# Step_Down_Module.net
KiCad netlist of a schematic drawn in EAGLE
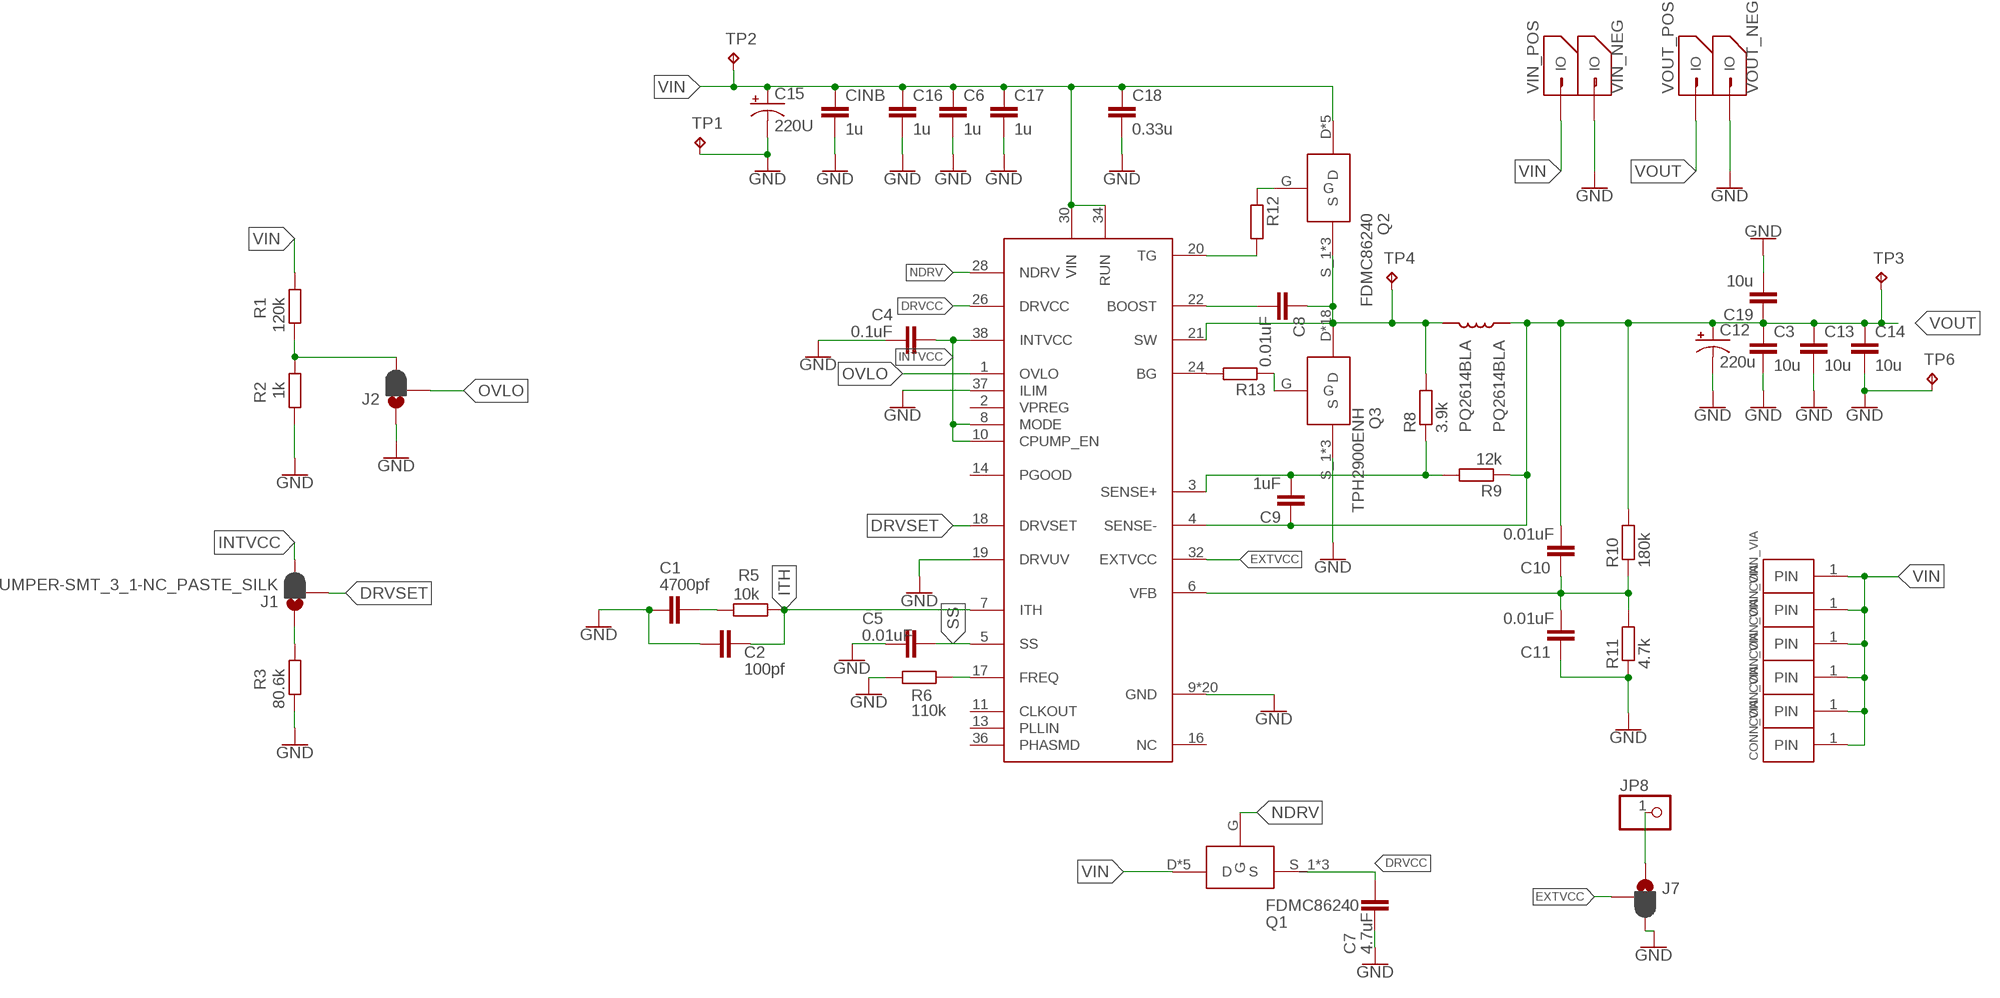
[diagram p0: schematic, sheet 1]

(export (version "E")
  (design (tool "Eeschema 10.0.6"))
  (components
    (comp (ref "C1")
      (value "4700pf")
      (footprint "eagle-import:C0805")
      (libsource (lib "eagle-import") (part "C-EUC0805"))
    )
    (comp (ref "C2")
      (value "100pf")
      (footprint "eagle-import:C0805")
      (libsource (lib "eagle-import") (part "C-EUC0805"))
    )
    (comp (ref "C3")
      (value "10u")
      (footprint "eagle-import:1210")
      (libsource (lib "eagle-import") (part "CAP_SMD_1210"))
    )
    (comp (ref "C4")
      (value "0.1uF")
      (footprint "eagle-import:C0805")
      (libsource (lib "eagle-import") (part "C-EUC0805"))
    )
    (comp (ref "C5")
      (value "0.01uF")
      (footprint "eagle-import:C0805")
      (libsource (lib "eagle-import") (part "C-EUC0805"))
    )
    (comp (ref "C6")
      (value "1u")
      (footprint "eagle-import:C2220K")
      (libsource (lib "eagle-import") (part "C-EUC2220K"))
    )
    (comp (ref "C7")
      (value "4.7uF")
      (footprint "eagle-import:C0805")
      (libsource (lib "eagle-import") (part "C-EUC0805"))
    )
    (comp (ref "C8")
      (value "0.01uF")
      (footprint "eagle-import:C0805")
      (libsource (lib "eagle-import") (part "C-EUC0805"))
    )
    (comp (ref "C9")
      (value "1uF")
      (footprint "eagle-import:C0805")
      (libsource (lib "eagle-import") (part "C-EUC0805"))
    )
    (comp (ref "C10")
      (value "0.01uF")
      (footprint "eagle-import:C0805")
      (libsource (lib "eagle-import") (part "C-EUC0805"))
    )
    (comp (ref "C11")
      (value "0.01uF")
      (footprint "eagle-import:C0805")
      (libsource (lib "eagle-import") (part "C-EUC0805"))
    )
    (comp (ref "C12")
      (value "220u")
      (footprint "eagle-import:CPOL-RADIAL-5MM-10MM")
      (libsource (lib "eagle-import") (part "1000UF-RADIAL-5MM-25V-20%"))
    )
    (comp (ref "C13")
      (value "10u")
      (footprint "eagle-import:1210")
      (libsource (lib "eagle-import") (part "CAP_SMD_1210"))
    )
    (comp (ref "C14")
      (value "10u")
      (footprint "eagle-import:1210")
      (libsource (lib "eagle-import") (part "CAP_SMD_1210"))
    )
    (comp (ref "C15")
      (value "220U")
      (footprint "eagle-import:CPOL-RADIAL-7.5MM-18MM")
      (libsource (lib "eagle-import") (part "220U"))
    )
    (comp (ref "C16")
      (value "1u")
      (footprint "eagle-import:C2220K")
      (libsource (lib "eagle-import") (part "C-EUC2220K"))
    )
    (comp (ref "C17")
      (value "1u")
      (footprint "eagle-import:C2220K")
      (libsource (lib "eagle-import") (part "C-EUC2220K"))
    )
    (comp (ref "C18")
      (value "0.33u")
      (footprint "eagle-import:C1812")
      (libsource (lib "eagle-import") (part "C-EUC1812"))
    )
    (comp (ref "C19")
      (value "10u")
      (footprint "eagle-import:1210")
      (libsource (lib "eagle-import") (part "CAP_SMD_1210"))
    )
    (comp (ref "CINB")
      (value "1u")
      (footprint "eagle-import:C2220K")
      (libsource (lib "eagle-import") (part "C-EUC2220K"))
    )
    (comp (ref "J1")
      (value "JUMPER-SMT_3_1-NC_PASTE_SILK")
      (footprint "eagle-import:SMT-JUMPER_3_1-NC_PASTE_SILK")
      (libsource (lib "eagle-import") (part "JUMPER-SMT_3_1-NC_PASTE_SILK"))
    )
    (comp (ref "J2")
      (value "JUMPER-SMT_3_1-NC_PASTE_SILK")
      (footprint "eagle-import:SMT-JUMPER_3_1-NC_PASTE_SILK")
      (libsource (lib "eagle-import") (part "JUMPER-SMT_3_1-NC_PASTE_SILK"))
    )
    (comp (ref "J7")
      (value "JUMPER-SMT_3_1-NC_PASTE_SILK")
      (footprint "eagle-import:SMT-JUMPER_3_1-NC_PASTE_SILK")
      (libsource (lib "eagle-import") (part "JUMPER-SMT_3_1-NC_PASTE_SILK"))
    )
    (comp (ref "JP8")
      (value "PINHD-1X1")
      (footprint "eagle-import:1X01")
      (libsource (lib "eagle-import") (part "PINHD-1X1"))
    )
    (comp (ref "L1")
      (value "PQ2614BLA")
      (footprint "eagle-import:PQ2614BLA")
      (libsource (lib "eagle-import") (part "PQ2614BLA"))
    )
    (comp (ref "Q1")
      (value "FDMC86240")
      (footprint "eagle-import:8-MLP_POWERWFDN")
      (libsource (lib "eagle-import") (part "FDMC86240"))
    )
    (comp (ref "Q2")
      (value "FDMC86240")
      (footprint "eagle-import:8-MLP_POWERWFDN")
      (libsource (lib "eagle-import") (part "FDMC86240"))
    )
    (comp (ref "Q3")
      (value "TPH2900ENH")
      (footprint "eagle-import:SOP_ADVANCE")
      (fields
        (field (name "MANUFACTURER_PART_NUMBER") "TPH8R80ANH")
        (field (name "MOUSER_PART_NUMBER") "1687790")
        (field (name "SPICEPREFIX") "Q")
      )
      (libsource (lib "eagle-import") (part "TPH2900ENH"))
    )
    (comp (ref "R1")
      (value "120k")
      (footprint "eagle-import:R0805")
      (libsource (lib "eagle-import") (part "R-EU_R0805"))
    )
    (comp (ref "R2")
      (value "1k")
      (footprint "eagle-import:R0805")
      (libsource (lib "eagle-import") (part "R-EU_R0805"))
    )
    (comp (ref "R3")
      (value "80.6k")
      (footprint "eagle-import:R0805")
      (libsource (lib "eagle-import") (part "R-EU_R0805"))
    )
    (comp (ref "R5")
      (value "10k")
      (footprint "eagle-import:R0805")
      (libsource (lib "eagle-import") (part "R-EU_R0805"))
    )
    (comp (ref "R6")
      (value "110k")
      (footprint "eagle-import:R0805")
      (libsource (lib "eagle-import") (part "R-EU_R0805"))
    )
    (comp (ref "R8")
      (value "3.9k")
      (footprint "eagle-import:0204_5")
      (libsource (lib "eagle-import") (part "resistor_348_R-EU_0204/5"))
    )
    (comp (ref "R9")
      (value "12k")
      (footprint "eagle-import:0204_5")
      (libsource (lib "eagle-import") (part "resistor_348_R-EU_0204/5"))
    )
    (comp (ref "R10")
      (value "180k")
      (footprint "eagle-import:R0805")
      (libsource (lib "eagle-import") (part "R-EU_R0805"))
    )
    (comp (ref "R11")
      (value "4.7k")
      (footprint "eagle-import:R0805")
      (libsource (lib "eagle-import") (part "R-EU_R0805"))
    )
    (comp (ref "R12")
      (value "R-EU_R0805")
      (footprint "eagle-import:R0805")
      (libsource (lib "eagle-import") (part "R-EU_R0805"))
    )
    (comp (ref "R13")
      (value "R-EU_R0805")
      (footprint "eagle-import:R0805")
      (libsource (lib "eagle-import") (part "R-EU_R0805"))
    )
    (comp (ref "TP1")
      (value "TPTP16R")
      (footprint "eagle-import:TP16R")
      (libsource (lib "eagle-import") (part "TPTP16R"))
    )
    (comp (ref "TP2")
      (value "TPTP16R")
      (footprint "eagle-import:TP16R")
      (libsource (lib "eagle-import") (part "TPTP16R"))
    )
    (comp (ref "TP3")
      (value "TPTP16R")
      (footprint "eagle-import:TP16R")
      (libsource (lib "eagle-import") (part "TPTP16R"))
    )
    (comp (ref "TP4")
      (value "TPTP16R")
      (footprint "eagle-import:TP16R")
      (libsource (lib "eagle-import") (part "TPTP16R"))
    )
    (comp (ref "TP6")
      (value "TPTP16R")
      (footprint "eagle-import:TP16R")
      (libsource (lib "eagle-import") (part "TPTP16R"))
    )
    (comp (ref "U$1")
      (value "CONN_VIA")
      (footprint "eagle-import:CONN_VIA")
      (libsource (lib "eagle-import") (part "CONN_VIA"))
    )
    (comp (ref "U$2")
      (value "CONN_VIA")
      (footprint "eagle-import:CONN_VIA")
      (libsource (lib "eagle-import") (part "CONN_VIA"))
    )
    (comp (ref "U$3")
      (value "CONN_VIA")
      (footprint "eagle-import:CONN_VIA")
      (libsource (lib "eagle-import") (part "CONN_VIA"))
    )
    (comp (ref "U$4")
      (value "CONN_VIA")
      (footprint "eagle-import:CONN_VIA")
      (libsource (lib "eagle-import") (part "CONN_VIA"))
    )
    (comp (ref "U$5")
      (value "CONN_VIA")
      (footprint "eagle-import:CONN_VIA")
      (libsource (lib "eagle-import") (part "CONN_VIA"))
    )
    (comp (ref "U$6")
      (value "CONN_VIA")
      (footprint "eagle-import:CONN_VIA")
      (libsource (lib "eagle-import") (part "CONN_VIA"))
    )
    (comp (ref "U1")
      (value "LTC3895_STEP_DOWN_DC-DC_CONVERTERSMD_TSSOP")
      (footprint "eagle-import:38_LEAD_TSSOP(FE38)")
      (libsource (lib "eagle-import") (part "LTC3895_STEP_DOWN_DC-DC_CONVERTERSMD_TSSOP"))
    )
    (comp (ref "VIN_NEG")
      (value "IO_PAD_SINGLE")
      (footprint "eagle-import:IO_SINGLE")
      (libsource (lib "eagle-import") (part "IO_PAD_SINGLE"))
    )
    (comp (ref "VIN_POS")
      (value "IO_PAD_SINGLE")
      (footprint "eagle-import:IO_SINGLE")
      (libsource (lib "eagle-import") (part "IO_PAD_SINGLE"))
    )
    (comp (ref "VOUT_NEG")
      (value "IO_PAD_SINGLE")
      (footprint "eagle-import:IO_SINGLE")
      (libsource (lib "eagle-import") (part "IO_PAD_SINGLE"))
    )
    (comp (ref "VOUT_POS")
      (value "IO_PAD_SINGLE")
      (footprint "eagle-import:IO_SINGLE")
      (libsource (lib "eagle-import") (part "IO_PAD_SINGLE"))
    )
  )
  (nets
    (net (code "1") (name "DRVCC") (class "Default")
      (node (ref "C7") (pin "1") (pinfunction "1_1") (pintype "passive"))
      (node (ref "Q1") (pin "S_1") (pinfunction "S_S_1") (pintype "bidirectional"))
      (node (ref "Q1") (pin "S_2") (pinfunction "S_S_2") (pintype "bidirectional"))
      (node (ref "Q1") (pin "S_3") (pinfunction "S_S_3") (pintype "bidirectional"))
      (node (ref "U1") (pin "26") (pinfunction "DRVCC_26") (pintype "bidirectional"))
    )
    (net (code "2") (name "DRVSET") (class "Default")
      (node (ref "J1") (pin "2") (pinfunction "2_2") (pintype "passive"))
      (node (ref "U1") (pin "18") (pinfunction "DRVSET_18") (pintype "bidirectional"))
    )
    (net (code "3") (name "EXTVCC") (class "Default")
      (node (ref "J7") (pin "2") (pinfunction "2_2") (pintype "passive"))
      (node (ref "U1") (pin "32") (pinfunction "EXTVCC_32") (pintype "bidirectional"))
    )
    (net (code "4") (name "GND") (class "Default")
      (node (ref "C1") (pin "2") (pinfunction "2_2") (pintype "passive"))
      (node (ref "C11") (pin "1") (pinfunction "1_1") (pintype "passive"))
      (node (ref "C12") (pin "-") (pinfunction "-_-") (pintype "passive"))
      (node (ref "C13") (pin "2") (pinfunction "2_2") (pintype "passive"))
      (node (ref "C14") (pin "2") (pinfunction "2_2") (pintype "passive"))
      (node (ref "C15") (pin "-") (pinfunction "-_-") (pintype "passive"))
      (node (ref "C16") (pin "2") (pinfunction "2_2") (pintype "passive"))
      (node (ref "C17") (pin "2") (pinfunction "2_2") (pintype "passive"))
      (node (ref "C18") (pin "2") (pinfunction "2_2") (pintype "passive"))
      (node (ref "C19") (pin "2") (pinfunction "2_2") (pintype "passive"))
      (node (ref "C2") (pin "2") (pinfunction "2_2") (pintype "passive"))
      (node (ref "C3") (pin "2") (pinfunction "2_2") (pintype "passive"))
      (node (ref "C4") (pin "1") (pinfunction "1_1") (pintype "passive"))
      (node (ref "C5") (pin "2") (pinfunction "2_2") (pintype "passive"))
      (node (ref "C6") (pin "2") (pinfunction "2_2") (pintype "passive"))
      (node (ref "C7") (pin "2") (pinfunction "2_2") (pintype "passive"))
      (node (ref "CINB") (pin "2") (pinfunction "2_2") (pintype "passive"))
      (node (ref "J2") (pin "1") (pinfunction "1_1") (pintype "passive"))
      (node (ref "J7") (pin "3") (pinfunction "3_3") (pintype "passive"))
      (node (ref "Q3") (pin "S_1") (pinfunction "S_S_1") (pintype "bidirectional"))
      (node (ref "Q3") (pin "S_2") (pinfunction "S_S_2") (pintype "bidirectional"))
      (node (ref "Q3") (pin "S_3") (pinfunction "S_S_3") (pintype "bidirectional"))
      (node (ref "R11") (pin "1") (pinfunction "1_1") (pintype "passive"))
      (node (ref "R2") (pin "2") (pinfunction "2_2") (pintype "passive"))
      (node (ref "R3") (pin "2") (pinfunction "2_2") (pintype "passive"))
      (node (ref "R6") (pin "1") (pinfunction "1_1") (pintype "passive"))
      (node (ref "TP1") (pin "TP") (pinfunction "TP_TP") (pintype "input"))
      (node (ref "TP6") (pin "TP") (pinfunction "TP_TP") (pintype "input"))
      (node (ref "U1") (pin "12") (pinfunction "GND_12") (pintype "bidirectional"))
      (node (ref "U1") (pin "15") (pinfunction "GND_15") (pintype "bidirectional"))
      (node (ref "U1") (pin "19") (pinfunction "DRVUV_19") (pintype "bidirectional"))
      (node (ref "U1") (pin "37") (pinfunction "ILIM_37") (pintype "bidirectional"))
      (node (ref "U1") (pin "39") (pinfunction "GND_39") (pintype "bidirectional"))
      (node (ref "U1") (pin "39_B") (pinfunction "GND_39_B") (pintype "bidirectional"))
      (node (ref "U1") (pin "9") (pinfunction "GND_9") (pintype "bidirectional"))
      (node (ref "U1") (pin "PWR_PAD1") (pinfunction "GND_PWR_PAD1") (pintype "bidirectional"))
      (node (ref "U1") (pin "PWR_PAD10") (pinfunction "GND_PWR_PAD10") (pintype "bidirectional"))
      (node (ref "U1") (pin "PWR_PAD11") (pinfunction "GND_PWR_PAD11") (pintype "bidirectional"))
      (node (ref "U1") (pin "PWR_PAD12") (pinfunction "GND_PWR_PAD12") (pintype "bidirectional"))
      (node (ref "U1") (pin "PWR_PAD13") (pinfunction "GND_PWR_PAD13") (pintype "bidirectional"))
      (node (ref "U1") (pin "PWR_PAD14") (pinfunction "GND_PWR_PAD14") (pintype "bidirectional"))
      (node (ref "U1") (pin "PWR_PAD15") (pinfunction "GND_PWR_PAD15") (pintype "bidirectional"))
      (node (ref "U1") (pin "PWR_PAD2") (pinfunction "GND_PWR_PAD2") (pintype "bidirectional"))
      (node (ref "U1") (pin "PWR_PAD3") (pinfunction "GND_PWR_PAD3") (pintype "bidirectional"))
      (node (ref "U1") (pin "PWR_PAD4") (pinfunction "GND_PWR_PAD4") (pintype "bidirectional"))
      (node (ref "U1") (pin "PWR_PAD5") (pinfunction "GND_PWR_PAD5") (pintype "bidirectional"))
      (node (ref "U1") (pin "PWR_PAD6") (pinfunction "GND_PWR_PAD6") (pintype "bidirectional"))
      (node (ref "U1") (pin "PWR_PAD7") (pinfunction "GND_PWR_PAD7") (pintype "bidirectional"))
      (node (ref "U1") (pin "PWR_PAD8") (pinfunction "GND_PWR_PAD8") (pintype "bidirectional"))
      (node (ref "U1") (pin "PWR_PAD9") (pinfunction "GND_PWR_PAD9") (pintype "bidirectional"))
      (node (ref "VIN_NEG") (pin "1") (pinfunction "IO_1") (pintype "bidirectional"))
      (node (ref "VIN_NEG") (pin "10") (pinfunction "IO_10") (pintype "bidirectional"))
      (node (ref "VIN_NEG") (pin "11") (pinfunction "IO_11") (pintype "bidirectional"))
      (node (ref "VIN_NEG") (pin "12") (pinfunction "IO_12") (pintype "bidirectional"))
      (node (ref "VIN_NEG") (pin "13") (pinfunction "IO_13") (pintype "bidirectional"))
      (node (ref "VIN_NEG") (pin "14") (pinfunction "IO_14") (pintype "bidirectional"))
      (node (ref "VIN_NEG") (pin "15") (pinfunction "IO_15") (pintype "bidirectional"))
      (node (ref "VIN_NEG") (pin "16") (pinfunction "IO_16") (pintype "bidirectional"))
      (node (ref "VIN_NEG") (pin "17") (pinfunction "IO_17") (pintype "bidirectional"))
      (node (ref "VIN_NEG") (pin "18") (pinfunction "IO_18") (pintype "bidirectional"))
      (node (ref "VIN_NEG") (pin "19") (pinfunction "IO_19") (pintype "bidirectional"))
      (node (ref "VIN_NEG") (pin "2") (pinfunction "IO_2") (pintype "bidirectional"))
      (node (ref "VIN_NEG") (pin "20") (pinfunction "IO_20") (pintype "bidirectional"))
      (node (ref "VIN_NEG") (pin "3") (pinfunction "IO_3") (pintype "bidirectional"))
      (node (ref "VIN_NEG") (pin "4") (pinfunction "IO_4") (pintype "bidirectional"))
      (node (ref "VIN_NEG") (pin "5") (pinfunction "IO_5") (pintype "bidirectional"))
      (node (ref "VIN_NEG") (pin "6") (pinfunction "IO_6") (pintype "bidirectional"))
      (node (ref "VIN_NEG") (pin "7") (pinfunction "IO_7") (pintype "bidirectional"))
      (node (ref "VIN_NEG") (pin "8") (pinfunction "IO_8") (pintype "bidirectional"))
      (node (ref "VIN_NEG") (pin "9") (pinfunction "IO_9") (pintype "bidirectional"))
      (node (ref "VIN_NEG") (pin "IO1") (pinfunction "IO_IO1") (pintype "bidirectional"))
      (node (ref "VIN_NEG") (pin "IO2") (pinfunction "IO_IO2") (pintype "bidirectional"))
      (node (ref "VOUT_NEG") (pin "1") (pinfunction "IO_1") (pintype "bidirectional"))
      (node (ref "VOUT_NEG") (pin "10") (pinfunction "IO_10") (pintype "bidirectional"))
      (node (ref "VOUT_NEG") (pin "11") (pinfunction "IO_11") (pintype "bidirectional"))
      (node (ref "VOUT_NEG") (pin "12") (pinfunction "IO_12") (pintype "bidirectional"))
      (node (ref "VOUT_NEG") (pin "13") (pinfunction "IO_13") (pintype "bidirectional"))
      (node (ref "VOUT_NEG") (pin "14") (pinfunction "IO_14") (pintype "bidirectional"))
      (node (ref "VOUT_NEG") (pin "15") (pinfunction "IO_15") (pintype "bidirectional"))
      (node (ref "VOUT_NEG") (pin "16") (pinfunction "IO_16") (pintype "bidirectional"))
      (node (ref "VOUT_NEG") (pin "17") (pinfunction "IO_17") (pintype "bidirectional"))
      (node (ref "VOUT_NEG") (pin "18") (pinfunction "IO_18") (pintype "bidirectional"))
      (node (ref "VOUT_NEG") (pin "19") (pinfunction "IO_19") (pintype "bidirectional"))
      (node (ref "VOUT_NEG") (pin "2") (pinfunction "IO_2") (pintype "bidirectional"))
      (node (ref "VOUT_NEG") (pin "20") (pinfunction "IO_20") (pintype "bidirectional"))
      (node (ref "VOUT_NEG") (pin "3") (pinfunction "IO_3") (pintype "bidirectional"))
      (node (ref "VOUT_NEG") (pin "4") (pinfunction "IO_4") (pintype "bidirectional"))
      (node (ref "VOUT_NEG") (pin "5") (pinfunction "IO_5") (pintype "bidirectional"))
      (node (ref "VOUT_NEG") (pin "6") (pinfunction "IO_6") (pintype "bidirectional"))
      (node (ref "VOUT_NEG") (pin "7") (pinfunction "IO_7") (pintype "bidirectional"))
      (node (ref "VOUT_NEG") (pin "8") (pinfunction "IO_8") (pintype "bidirectional"))
      (node (ref "VOUT_NEG") (pin "9") (pinfunction "IO_9") (pintype "bidirectional"))
      (node (ref "VOUT_NEG") (pin "IO1") (pinfunction "IO_IO1") (pintype "bidirectional"))
      (node (ref "VOUT_NEG") (pin "IO2") (pinfunction "IO_IO2") (pintype "bidirectional"))
    )
    (net (code "5") (name "INTVCC") (class "Default")
      (node (ref "C4") (pin "2") (pinfunction "2_2") (pintype "passive"))
      (node (ref "J1") (pin "3") (pinfunction "3_3") (pintype "passive"))
      (node (ref "U1") (pin "10") (pinfunction "CPUMP_EN_10") (pintype "bidirectional"))
      (node (ref "U1") (pin "38") (pinfunction "INTVCC_38") (pintype "bidirectional"))
      (node (ref "U1") (pin "8") (pinfunction "MODE_8") (pintype "bidirectional"))
    )
    (net (code "6") (name "ITH") (class "Default")
      (node (ref "C2") (pin "1") (pinfunction "1_1") (pintype "passive"))
      (node (ref "R5") (pin "1") (pinfunction "1_1") (pintype "passive"))
      (node (ref "U1") (pin "7") (pinfunction "ITH_7") (pintype "bidirectional"))
    )
    (net (code "7") (name "NDRV") (class "Default")
      (node (ref "Q1") (pin "G") (pinfunction "G_G") (pintype "bidirectional"))
      (node (ref "U1") (pin "28") (pinfunction "NDRV_28") (pintype "bidirectional"))
    )
    (net (code "8") (name "Net-(C1-Pad1)") (class "Default")
      (node (ref "C1") (pin "1") (pinfunction "1_1") (pintype "passive"))
      (node (ref "R5") (pin "2") (pinfunction "2_2") (pintype "passive"))
    )
    (net (code "9") (name "Net-(J1-Pad1)") (class "Default")
      (node (ref "J1") (pin "1") (pinfunction "1_1") (pintype "passive"))
      (node (ref "R3") (pin "1") (pinfunction "1_1") (pintype "passive"))
    )
    (net (code "10") (name "Net-(J2-Pad3)") (class "Default")
      (node (ref "J2") (pin "3") (pinfunction "3_3") (pintype "passive"))
      (node (ref "R1") (pin "2") (pinfunction "2_2") (pintype "passive"))
      (node (ref "R2") (pin "1") (pinfunction "1_1") (pintype "passive"))
    )
    (net (code "11") (name "Net-(J7-Pad1)") (class "Default")
      (node (ref "J7") (pin "1") (pinfunction "1_1") (pintype "passive"))
      (node (ref "JP8") (pin "1") (pinfunction "1_1") (pintype "passive"))
    )
    (net (code "12") (name "Net-(L1-P$2)") (class "Default")
      (node (ref "C8") (pin "1") (pinfunction "1_1") (pintype "passive"))
      (node (ref "L1") (pin "P1") (pinfunction "P$2_P1") (pintype "bidirectional"))
      (node (ref "Q2") (pin "S_1") (pinfunction "S_S_1") (pintype "bidirectional"))
      (node (ref "Q2") (pin "S_2") (pinfunction "S_S_2") (pintype "bidirectional"))
      (node (ref "Q2") (pin "S_3") (pinfunction "S_S_3") (pintype "bidirectional"))
      (node (ref "Q3") (pin "D") (pinfunction "D_D") (pintype "bidirectional"))
      (node (ref "Q3") (pin "D1") (pinfunction "D_D1") (pintype "bidirectional"))
      (node (ref "Q3") (pin "D_1") (pinfunction "D_D_1") (pintype "bidirectional"))
      (node (ref "Q3") (pin "D_2") (pinfunction "D_D_2") (pintype "bidirectional"))
      (node (ref "Q3") (pin "D_3") (pinfunction "D_D_3") (pintype "bidirectional"))
      (node (ref "Q3") (pin "D_4") (pinfunction "D_D_4") (pintype "bidirectional"))
      (node (ref "Q3") (pin "PWR_PAD1") (pinfunction "D_PWR_PAD1") (pintype "bidirectional"))
      (node (ref "Q3") (pin "PWR_PAD10") (pinfunction "D_PWR_PAD10") (pintype "bidirectional"))
      (node (ref "Q3") (pin "PWR_PAD11") (pinfunction "D_PWR_PAD11") (pintype "bidirectional"))
      (node (ref "Q3") (pin "PWR_PAD12") (pinfunction "D_PWR_PAD12") (pintype "bidirectional"))
      (node (ref "Q3") (pin "PWR_PAD2") (pinfunction "D_PWR_PAD2") (pintype "bidirectional"))
      (node (ref "Q3") (pin "PWR_PAD3") (pinfunction "D_PWR_PAD3") (pintype "bidirectional"))
      (node (ref "Q3") (pin "PWR_PAD4") (pinfunction "D_PWR_PAD4") (pintype "bidirectional"))
      (node (ref "Q3") (pin "PWR_PAD5") (pinfunction "D_PWR_PAD5") (pintype "bidirectional"))
      (node (ref "Q3") (pin "PWR_PAD6") (pinfunction "D_PWR_PAD6") (pintype "bidirectional"))
      (node (ref "Q3") (pin "PWR_PAD7") (pinfunction "D_PWR_PAD7") (pintype "bidirectional"))
      (node (ref "Q3") (pin "PWR_PAD8") (pinfunction "D_PWR_PAD8") (pintype "bidirectional"))
      (node (ref "Q3") (pin "PWR_PAD9") (pinfunction "D_PWR_PAD9") (pintype "bidirectional"))
      (node (ref "R8") (pin "2") (pinfunction "2_2") (pintype "passive"))
      (node (ref "TP4") (pin "TP") (pinfunction "TP_TP") (pintype "input"))
      (node (ref "U1") (pin "21") (pinfunction "SW_21") (pintype "bidirectional"))
    )
    (net (code "13") (name "Net-(Q2-PadG)") (class "Default")
      (node (ref "Q2") (pin "G") (pinfunction "G_G") (pintype "bidirectional"))
      (node (ref "R12") (pin "1") (pinfunction "1_1") (pintype "passive"))
    )
    (net (code "14") (name "Net-(Q3-PadG)") (class "Default")
      (node (ref "Q3") (pin "G") (pinfunction "G_G") (pintype "bidirectional"))
      (node (ref "R13") (pin "1") (pinfunction "1_1") (pintype "passive"))
    )
    (net (code "15") (name "Net-(U1-BG)") (class "Default")
      (node (ref "R13") (pin "2") (pinfunction "2_2") (pintype "passive"))
      (node (ref "U1") (pin "24") (pinfunction "BG_24") (pintype "bidirectional"))
    )
    (net (code "16") (name "Net-(U1-BOOST)") (class "Default")
      (node (ref "C8") (pin "2") (pinfunction "2_2") (pintype "passive"))
      (node (ref "U1") (pin "22") (pinfunction "BOOST_22") (pintype "bidirectional"))
    )
    (net (code "17") (name "Net-(U1-FREQ)") (class "Default")
      (node (ref "R6") (pin "2") (pinfunction "2_2") (pintype "passive"))
      (node (ref "U1") (pin "17") (pinfunction "FREQ_17") (pintype "bidirectional"))
    )
    (net (code "18") (name "Net-(U1-SENSE+)") (class "Default")
      (node (ref "C9") (pin "2") (pinfunction "2_2") (pintype "passive"))
      (node (ref "R8") (pin "1") (pinfunction "1_1") (pintype "passive"))
      (node (ref "R9") (pin "2") (pinfunction "2_2") (pintype "passive"))
      (node (ref "U1") (pin "3") (pinfunction "SENSE+_3") (pintype "bidirectional"))
    )
    (net (code "19") (name "Net-(U1-TG)") (class "Default")
      (node (ref "R12") (pin "2") (pinfunction "2_2") (pintype "passive"))
      (node (ref "U1") (pin "20") (pinfunction "TG_20") (pintype "bidirectional"))
    )
    (net (code "20") (name "Net-(U1-VFB)") (class "Default")
      (node (ref "C10") (pin "1") (pinfunction "1_1") (pintype "passive"))
      (node (ref "C11") (pin "2") (pinfunction "2_2") (pintype "passive"))
      (node (ref "R10") (pin "1") (pinfunction "1_1") (pintype "passive"))
      (node (ref "R11") (pin "2") (pinfunction "2_2") (pintype "passive"))
      (node (ref "U1") (pin "6") (pinfunction "VFB_6") (pintype "bidirectional"))
    )
    (net (code "21") (name "OVLO") (class "Default")
      (node (ref "J2") (pin "2") (pinfunction "2_2") (pintype "passive"))
      (node (ref "U1") (pin "1") (pinfunction "OVLO_1") (pintype "bidirectional"))
    )
    (net (code "22") (name "SS") (class "Default")
      (node (ref "C5") (pin "1") (pinfunction "1_1") (pintype "passive"))
      (node (ref "U1") (pin "5") (pinfunction "SS_5") (pintype "bidirectional"))
    )
    (net (code "23") (name "VIN") (class "Default")
      (node (ref "C15") (pin "+") (pinfunction "+_+") (pintype "passive"))
      (node (ref "C16") (pin "1") (pinfunction "1_1") (pintype "passive"))
      (node (ref "C17") (pin "1") (pinfunction "1_1") (pintype "passive"))
      (node (ref "C18") (pin "1") (pinfunction "1_1") (pintype "passive"))
      (node (ref "C6") (pin "1") (pinfunction "1_1") (pintype "passive"))
      (node (ref "CINB") (pin "1") (pinfunction "1_1") (pintype "passive"))
      (node (ref "Q1") (pin "D") (pinfunction "D_D") (pintype "bidirectional"))
      (node (ref "Q1") (pin "D_1") (pinfunction "D_D_1") (pintype "bidirectional"))
      (node (ref "Q1") (pin "D_2") (pinfunction "D_D_2") (pintype "bidirectional"))
      (node (ref "Q1") (pin "D_3") (pinfunction "D_D_3") (pintype "bidirectional"))
      (node (ref "Q1") (pin "D_4") (pinfunction "D_D_4") (pintype "bidirectional"))
      (node (ref "Q2") (pin "D") (pinfunction "D_D") (pintype "bidirectional"))
      (node (ref "Q2") (pin "D_1") (pinfunction "D_D_1") (pintype "bidirectional"))
      (node (ref "Q2") (pin "D_2") (pinfunction "D_D_2") (pintype "bidirectional"))
      (node (ref "Q2") (pin "D_3") (pinfunction "D_D_3") (pintype "bidirectional"))
      (node (ref "Q2") (pin "D_4") (pinfunction "D_D_4") (pintype "bidirectional"))
      (node (ref "R1") (pin "1") (pinfunction "1_1") (pintype "passive"))
      (node (ref "TP2") (pin "TP") (pinfunction "TP_TP") (pintype "input"))
      (node (ref "U$1") (pin "1") (pinfunction "PIN_1") (pintype "bidirectional"))
      (node (ref "U$2") (pin "1") (pinfunction "PIN_1") (pintype "bidirectional"))
      (node (ref "U$3") (pin "1") (pinfunction "PIN_1") (pintype "bidirectional"))
      (node (ref "U$4") (pin "1") (pinfunction "PIN_1") (pintype "bidirectional"))
      (node (ref "U$5") (pin "1") (pinfunction "PIN_1") (pintype "bidirectional"))
      (node (ref "U$6") (pin "1") (pinfunction "PIN_1") (pintype "bidirectional"))
      (node (ref "U1") (pin "30") (pinfunction "VIN_30") (pintype "bidirectional"))
      (node (ref "U1") (pin "34") (pinfunction "RUN_34") (pintype "bidirectional"))
      (node (ref "VIN_POS") (pin "1") (pinfunction "IO_1") (pintype "bidirectional"))
      (node (ref "VIN_POS") (pin "10") (pinfunction "IO_10") (pintype "bidirectional"))
      (node (ref "VIN_POS") (pin "11") (pinfunction "IO_11") (pintype "bidirectional"))
      (node (ref "VIN_POS") (pin "12") (pinfunction "IO_12") (pintype "bidirectional"))
      (node (ref "VIN_POS") (pin "13") (pinfunction "IO_13") (pintype "bidirectional"))
      (node (ref "VIN_POS") (pin "14") (pinfunction "IO_14") (pintype "bidirectional"))
      (node (ref "VIN_POS") (pin "15") (pinfunction "IO_15") (pintype "bidirectional"))
      (node (ref "VIN_POS") (pin "16") (pinfunction "IO_16") (pintype "bidirectional"))
      (node (ref "VIN_POS") (pin "17") (pinfunction "IO_17") (pintype "bidirectional"))
      (node (ref "VIN_POS") (pin "18") (pinfunction "IO_18") (pintype "bidirectional"))
      (node (ref "VIN_POS") (pin "19") (pinfunction "IO_19") (pintype "bidirectional"))
      (node (ref "VIN_POS") (pin "2") (pinfunction "IO_2") (pintype "bidirectional"))
      (node (ref "VIN_POS") (pin "20") (pinfunction "IO_20") (pintype "bidirectional"))
      (node (ref "VIN_POS") (pin "3") (pinfunction "IO_3") (pintype "bidirectional"))
      (node (ref "VIN_POS") (pin "4") (pinfunction "IO_4") (pintype "bidirectional"))
      (node (ref "VIN_POS") (pin "5") (pinfunction "IO_5") (pintype "bidirectional"))
      (node (ref "VIN_POS") (pin "6") (pinfunction "IO_6") (pintype "bidirectional"))
      (node (ref "VIN_POS") (pin "7") (pinfunction "IO_7") (pintype "bidirectional"))
      (node (ref "VIN_POS") (pin "8") (pinfunction "IO_8") (pintype "bidirectional"))
      (node (ref "VIN_POS") (pin "9") (pinfunction "IO_9") (pintype "bidirectional"))
      (node (ref "VIN_POS") (pin "IO1") (pinfunction "IO_IO1") (pintype "bidirectional"))
      (node (ref "VIN_POS") (pin "IO2") (pinfunction "IO_IO2") (pintype "bidirectional"))
    )
    (net (code "24") (name "VOUT") (class "Default")
      (node (ref "C10") (pin "2") (pinfunction "2_2") (pintype "passive"))
      (node (ref "C12") (pin "+") (pinfunction "+_+") (pintype "passive"))
      (node (ref "C13") (pin "1") (pinfunction "1_1") (pintype "passive"))
      (node (ref "C14") (pin "1") (pinfunction "1_1") (pintype "passive"))
      (node (ref "C19") (pin "1") (pinfunction "1_1") (pintype "passive"))
      (node (ref "C3") (pin "1") (pinfunction "1_1") (pintype "passive"))
      (node (ref "C9") (pin "1") (pinfunction "1_1") (pintype "passive"))
      (node (ref "L1") (pin "P2") (pinfunction "P$1_P2") (pintype "bidirectional"))
      (node (ref "R10") (pin "2") (pinfunction "2_2") (pintype "passive"))
      (node (ref "R9") (pin "1") (pinfunction "1_1") (pintype "passive"))
      (node (ref "TP3") (pin "TP") (pinfunction "TP_TP") (pintype "input"))
      (node (ref "U1") (pin "4") (pinfunction "SENSE-_4") (pintype "bidirectional"))
      (node (ref "VOUT_POS") (pin "1") (pinfunction "IO_1") (pintype "bidirectional"))
      (node (ref "VOUT_POS") (pin "10") (pinfunction "IO_10") (pintype "bidirectional"))
      (node (ref "VOUT_POS") (pin "11") (pinfunction "IO_11") (pintype "bidirectional"))
      (node (ref "VOUT_POS") (pin "12") (pinfunction "IO_12") (pintype "bidirectional"))
      (node (ref "VOUT_POS") (pin "13") (pinfunction "IO_13") (pintype "bidirectional"))
      (node (ref "VOUT_POS") (pin "14") (pinfunction "IO_14") (pintype "bidirectional"))
      (node (ref "VOUT_POS") (pin "15") (pinfunction "IO_15") (pintype "bidirectional"))
      (node (ref "VOUT_POS") (pin "16") (pinfunction "IO_16") (pintype "bidirectional"))
      (node (ref "VOUT_POS") (pin "17") (pinfunction "IO_17") (pintype "bidirectional"))
      (node (ref "VOUT_POS") (pin "18") (pinfunction "IO_18") (pintype "bidirectional"))
      (node (ref "VOUT_POS") (pin "19") (pinfunction "IO_19") (pintype "bidirectional"))
      (node (ref "VOUT_POS") (pin "2") (pinfunction "IO_2") (pintype "bidirectional"))
      (node (ref "VOUT_POS") (pin "20") (pinfunction "IO_20") (pintype "bidirectional"))
      (node (ref "VOUT_POS") (pin "3") (pinfunction "IO_3") (pintype "bidirectional"))
      (node (ref "VOUT_POS") (pin "4") (pinfunction "IO_4") (pintype "bidirectional"))
      (node (ref "VOUT_POS") (pin "5") (pinfunction "IO_5") (pintype "bidirectional"))
      (node (ref "VOUT_POS") (pin "6") (pinfunction "IO_6") (pintype "bidirectional"))
      (node (ref "VOUT_POS") (pin "7") (pinfunction "IO_7") (pintype "bidirectional"))
      (node (ref "VOUT_POS") (pin "8") (pinfunction "IO_8") (pintype "bidirectional"))
      (node (ref "VOUT_POS") (pin "9") (pinfunction "IO_9") (pintype "bidirectional"))
      (node (ref "VOUT_POS") (pin "IO1") (pinfunction "IO_IO1") (pintype "bidirectional"))
      (node (ref "VOUT_POS") (pin "IO2") (pinfunction "IO_IO2") (pintype "bidirectional"))
    )
    (net (code "25") (name "unconnected-(U1-CLKOUT-Pad11)") (class "Default")
      (node (ref "U1") (pin "11") (pinfunction "CLKOUT_11") (pintype "bidirectional"))
    )
    (net (code "26") (name "unconnected-(U1-NC-Pad16)") (class "Default")
      (node (ref "U1") (pin "16") (pinfunction "NC_16") (pintype "bidirectional"))
    )
    (net (code "27") (name "unconnected-(U1-PGOOD-Pad14)") (class "Default")
      (node (ref "U1") (pin "14") (pinfunction "PGOOD_14") (pintype "bidirectional"))
    )
    (net (code "28") (name "unconnected-(U1-PHASMD-Pad36)") (class "Default")
      (node (ref "U1") (pin "36") (pinfunction "PHASMD_36") (pintype "bidirectional"))
    )
    (net (code "29") (name "unconnected-(U1-PLLIN-Pad13)") (class "Default")
      (node (ref "U1") (pin "13") (pinfunction "PLLIN_13") (pintype "bidirectional"))
    )
    (net (code "30") (name "unconnected-(U1-VPREG-Pad2)") (class "Default")
      (node (ref "U1") (pin "2") (pinfunction "VPREG_2") (pintype "bidirectional"))
    )
  )
)
